# elysium_v0_6.net
KiCad netlist of a schematic drawn in EAGLE
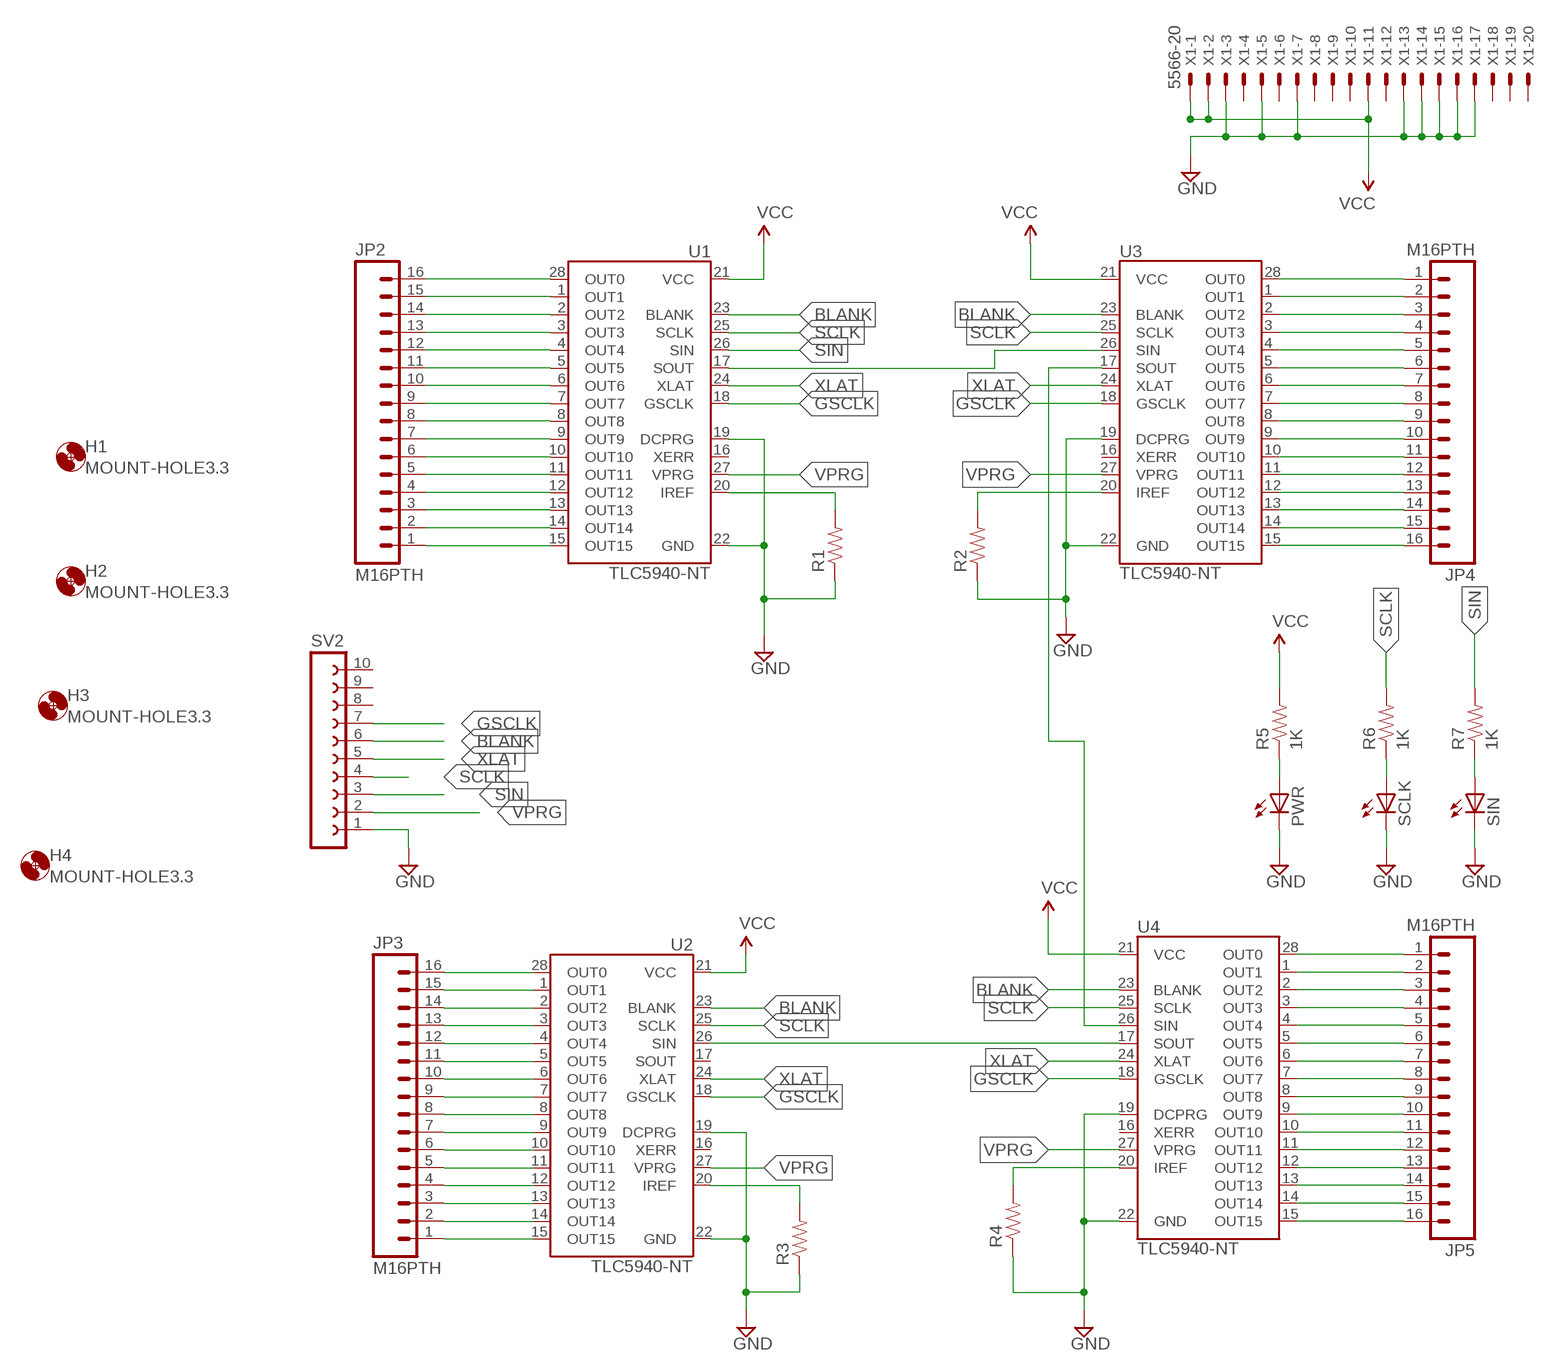
[diagram p0: schematic, sheet 1]

(export (version "E")
  (design (tool "Eeschema 10.0.6"))
  (components
    (comp (ref "H1")
      (value "MOUNT-HOLE3.3")
      (footprint "eagle-import:3,3")
      (libsource (lib "eagle-import") (part "MOUNT-HOLE3.3"))
    )
    (comp (ref "H2")
      (value "MOUNT-HOLE3.3")
      (footprint "eagle-import:3,3")
      (libsource (lib "eagle-import") (part "MOUNT-HOLE3.3"))
    )
    (comp (ref "H3")
      (value "MOUNT-HOLE3.3")
      (footprint "eagle-import:3,3")
      (libsource (lib "eagle-import") (part "MOUNT-HOLE3.3"))
    )
    (comp (ref "H4")
      (value "MOUNT-HOLE3.3")
      (footprint "eagle-import:3,3")
      (libsource (lib "eagle-import") (part "MOUNT-HOLE3.3"))
    )
    (comp (ref "JP2")
      (value "M16PTH")
      (footprint "eagle-import:1X16")
      (libsource (lib "eagle-import") (part "M16PTH"))
    )
    (comp (ref "JP3")
      (value "M16PTH")
      (footprint "eagle-import:1X16")
      (libsource (lib "eagle-import") (part "M16PTH"))
    )
    (comp (ref "JP4")
      (value "M16PTH")
      (footprint "eagle-import:1X16")
      (libsource (lib "eagle-import") (part "M16PTH"))
    )
    (comp (ref "JP5")
      (value "M16PTH")
      (footprint "eagle-import:1X16")
      (libsource (lib "eagle-import") (part "M16PTH"))
    )
    (comp (ref "PWR")
      (value "LED5MM")
      (footprint "eagle-import:LED5MM")
      (libsource (lib "eagle-import") (part "LED5MM"))
    )
    (comp (ref "R1")
      (value "RESISTOREZ")
      (footprint "eagle-import:AXIAL-0.3EZ")
      (libsource (lib "eagle-import") (part "RESISTOREZ"))
    )
    (comp (ref "R2")
      (value "RESISTOREZ")
      (footprint "eagle-import:AXIAL-0.3EZ")
      (libsource (lib "eagle-import") (part "RESISTOREZ"))
    )
    (comp (ref "R3")
      (value "RESISTOREZ")
      (footprint "eagle-import:AXIAL-0.3EZ")
      (libsource (lib "eagle-import") (part "RESISTOREZ"))
    )
    (comp (ref "R4")
      (value "RESISTOREZ")
      (footprint "eagle-import:AXIAL-0.3EZ")
      (libsource (lib "eagle-import") (part "RESISTOREZ"))
    )
    (comp (ref "R5")
      (value "1K")
      (footprint "eagle-import:AXIAL-0.3EZ")
      (libsource (lib "eagle-import") (part "RESISTOREZ"))
    )
    (comp (ref "R6")
      (value "1K")
      (footprint "eagle-import:AXIAL-0.3EZ")
      (libsource (lib "eagle-import") (part "RESISTOREZ"))
    )
    (comp (ref "R7")
      (value "1K")
      (footprint "eagle-import:AXIAL-0.3EZ")
      (libsource (lib "eagle-import") (part "RESISTOREZ"))
    )
    (comp (ref "SCLK")
      (value "LED5MM")
      (footprint "eagle-import:LED5MM")
      (libsource (lib "eagle-import") (part "LED5MM"))
    )
    (comp (ref "SIN")
      (value "LED5MM")
      (footprint "eagle-import:LED5MM")
      (libsource (lib "eagle-import") (part "LED5MM"))
    )
    (comp (ref "SV2")
      (value "FE10-1")
      (footprint "eagle-import:FE10")
      (libsource (lib "eagle-import") (part "FE10-1"))
    )
    (comp (ref "U1")
      (value "TLC5940-NT")
      (footprint "eagle-import:DIL28-3")
      (libsource (lib "eagle-import") (part "TLC5940-NT"))
    )
    (comp (ref "U2")
      (value "TLC5940-NT")
      (footprint "eagle-import:DIL28-3")
      (libsource (lib "eagle-import") (part "TLC5940-NT"))
    )
    (comp (ref "U3")
      (value "TLC5940-NT")
      (footprint "eagle-import:DIL28-3")
      (libsource (lib "eagle-import") (part "TLC5940-NT"))
    )
    (comp (ref "U4")
      (value "TLC5940-NT")
      (footprint "eagle-import:DIL28-3")
      (libsource (lib "eagle-import") (part "TLC5940-NT"))
    )
    (comp (ref "X1")
      (value "5566-20")
      (footprint "eagle-import:5566-20")
      (libsource (lib "eagle-import") (part "5566-20"))
    )
  )
  (nets
    (net (code "1") (name "BLANK") (class "Default")
      (node (ref "SV2") (pin "6") (pinfunction "6_6") (pintype "passive"))
      (node (ref "U1") (pin "23") (pinfunction "BLANK_23") (pintype "bidirectional"))
      (node (ref "U2") (pin "23") (pinfunction "BLANK_23") (pintype "bidirectional"))
      (node (ref "U3") (pin "23") (pinfunction "BLANK_23") (pintype "bidirectional"))
      (node (ref "U4") (pin "23") (pinfunction "BLANK_23") (pintype "bidirectional"))
    )
    (net (code "2") (name "GND") (class "Default")
      (node (ref "PWR") (pin "K") (pinfunction "C_K") (pintype "passive"))
      (node (ref "R1") (pin "P$1") (pinfunction "1_P$1") (pintype "passive"))
      (node (ref "R2") (pin "P$1") (pinfunction "1_P$1") (pintype "passive"))
      (node (ref "R3") (pin "P$1") (pinfunction "1_P$1") (pintype "passive"))
      (node (ref "R4") (pin "P$1") (pinfunction "1_P$1") (pintype "passive"))
      (node (ref "SCLK") (pin "K") (pinfunction "C_K") (pintype "passive"))
      (node (ref "SIN") (pin "K") (pinfunction "C_K") (pintype "passive"))
      (node (ref "SV2") (pin "1") (pinfunction "1_1") (pintype "passive"))
      (node (ref "U1") (pin "19") (pinfunction "DCPRG_19") (pintype "bidirectional"))
      (node (ref "U1") (pin "22") (pinfunction "GND_22") (pintype "bidirectional"))
      (node (ref "U2") (pin "19") (pinfunction "DCPRG_19") (pintype "bidirectional"))
      (node (ref "U2") (pin "22") (pinfunction "GND_22") (pintype "bidirectional"))
      (node (ref "U3") (pin "19") (pinfunction "DCPRG_19") (pintype "bidirectional"))
      (node (ref "U3") (pin "22") (pinfunction "GND_22") (pintype "bidirectional"))
      (node (ref "U4") (pin "19") (pinfunction "DCPRG_19") (pintype "bidirectional"))
      (node (ref "U4") (pin "22") (pinfunction "GND_22") (pintype "bidirectional"))
      (node (ref "X1") (pin "13") (pinfunction "S_13") (pintype "passive"))
      (node (ref "X1") (pin "14") (pinfunction "S_14") (pintype "passive"))
      (node (ref "X1") (pin "15") (pinfunction "S_15") (pintype "passive"))
      (node (ref "X1") (pin "16") (pinfunction "S_16") (pintype "passive"))
      (node (ref "X1") (pin "17") (pinfunction "S_17") (pintype "passive"))
      (node (ref "X1") (pin "3") (pinfunction "S_3") (pintype "passive"))
      (node (ref "X1") (pin "5") (pinfunction "S_5") (pintype "passive"))
      (node (ref "X1") (pin "7") (pinfunction "S_7") (pintype "passive"))
    )
    (net (code "3") (name "GSCLK") (class "Default")
      (node (ref "SV2") (pin "7") (pinfunction "7_7") (pintype "passive"))
      (node (ref "U1") (pin "18") (pinfunction "GSCLK_18") (pintype "bidirectional"))
      (node (ref "U2") (pin "18") (pinfunction "GSCLK_18") (pintype "bidirectional"))
      (node (ref "U3") (pin "18") (pinfunction "GSCLK_18") (pintype "bidirectional"))
      (node (ref "U4") (pin "18") (pinfunction "GSCLK_18") (pintype "bidirectional"))
    )
    (net (code "4") (name "Net-(R1-2)") (class "Default")
      (node (ref "R1") (pin "P$2") (pinfunction "2_P$2") (pintype "passive"))
      (node (ref "U1") (pin "20") (pinfunction "IREF_20") (pintype "bidirectional"))
    )
    (net (code "5") (name "Net-(R2-2)") (class "Default")
      (node (ref "R2") (pin "P$2") (pinfunction "2_P$2") (pintype "passive"))
      (node (ref "U3") (pin "20") (pinfunction "IREF_20") (pintype "bidirectional"))
    )
    (net (code "6") (name "Net-(R3-2)") (class "Default")
      (node (ref "R3") (pin "P$2") (pinfunction "2_P$2") (pintype "passive"))
      (node (ref "U2") (pin "20") (pinfunction "IREF_20") (pintype "bidirectional"))
    )
    (net (code "7") (name "Net-(R4-2)") (class "Default")
      (node (ref "R4") (pin "P$2") (pinfunction "2_P$2") (pintype "passive"))
      (node (ref "U4") (pin "20") (pinfunction "IREF_20") (pintype "bidirectional"))
    )
    (net (code "8") (name "Net-(R5-1)") (class "Default")
      (node (ref "PWR") (pin "A") (pinfunction "A_A") (pintype "passive"))
      (node (ref "R5") (pin "P$1") (pinfunction "1_P$1") (pintype "passive"))
    )
    (net (code "9") (name "Net-(R6-1)") (class "Default")
      (node (ref "R6") (pin "P$1") (pinfunction "1_P$1") (pintype "passive"))
      (node (ref "SCLK") (pin "A") (pinfunction "A_A") (pintype "passive"))
    )
    (net (code "10") (name "Net-(R7-1)") (class "Default")
      (node (ref "R7") (pin "P$1") (pinfunction "1_P$1") (pintype "passive"))
      (node (ref "SIN") (pin "A") (pinfunction "A_A") (pintype "passive"))
    )
    (net (code "11") (name "Net-(U1-OUT0)") (class "Default")
      (node (ref "JP2") (pin "16") (pinfunction "16_16") (pintype "passive"))
      (node (ref "U1") (pin "28") (pinfunction "OUT0_28") (pintype "bidirectional"))
    )
    (net (code "12") (name "Net-(U1-OUT1)") (class "Default")
      (node (ref "JP2") (pin "15") (pinfunction "15_15") (pintype "passive"))
      (node (ref "U1") (pin "1") (pinfunction "OUT1_1") (pintype "bidirectional"))
    )
    (net (code "13") (name "Net-(U1-OUT2)") (class "Default")
      (node (ref "JP2") (pin "14") (pinfunction "14_14") (pintype "passive"))
      (node (ref "U1") (pin "2") (pinfunction "OUT2_2") (pintype "bidirectional"))
    )
    (net (code "14") (name "Net-(U1-OUT3)") (class "Default")
      (node (ref "JP2") (pin "13") (pinfunction "13_13") (pintype "passive"))
      (node (ref "U1") (pin "3") (pinfunction "OUT3_3") (pintype "bidirectional"))
    )
    (net (code "15") (name "Net-(U1-OUT4)") (class "Default")
      (node (ref "JP2") (pin "12") (pinfunction "12_12") (pintype "passive"))
      (node (ref "U1") (pin "4") (pinfunction "OUT4_4") (pintype "bidirectional"))
    )
    (net (code "16") (name "Net-(U1-OUT5)") (class "Default")
      (node (ref "JP2") (pin "11") (pinfunction "11_11") (pintype "passive"))
      (node (ref "U1") (pin "5") (pinfunction "OUT5_5") (pintype "bidirectional"))
    )
    (net (code "17") (name "Net-(U1-OUT6)") (class "Default")
      (node (ref "JP2") (pin "10") (pinfunction "10_10") (pintype "passive"))
      (node (ref "U1") (pin "6") (pinfunction "OUT6_6") (pintype "bidirectional"))
    )
    (net (code "18") (name "Net-(U1-OUT7)") (class "Default")
      (node (ref "JP2") (pin "9") (pinfunction "9_9") (pintype "passive"))
      (node (ref "U1") (pin "7") (pinfunction "OUT7_7") (pintype "bidirectional"))
    )
    (net (code "19") (name "Net-(U1-OUT8)") (class "Default")
      (node (ref "JP2") (pin "8") (pinfunction "8_8") (pintype "passive"))
      (node (ref "U1") (pin "8") (pinfunction "OUT8_8") (pintype "bidirectional"))
    )
    (net (code "20") (name "Net-(U1-OUT9)") (class "Default")
      (node (ref "JP2") (pin "7") (pinfunction "7_7") (pintype "passive"))
      (node (ref "U1") (pin "9") (pinfunction "OUT9_9") (pintype "bidirectional"))
    )
    (net (code "21") (name "Net-(U1-OUT10)") (class "Default")
      (node (ref "JP2") (pin "6") (pinfunction "6_6") (pintype "passive"))
      (node (ref "U1") (pin "10") (pinfunction "OUT10_10") (pintype "bidirectional"))
    )
    (net (code "22") (name "Net-(U1-OUT11)") (class "Default")
      (node (ref "JP2") (pin "5") (pinfunction "5_5") (pintype "passive"))
      (node (ref "U1") (pin "11") (pinfunction "OUT11_11") (pintype "bidirectional"))
    )
    (net (code "23") (name "Net-(U1-OUT12)") (class "Default")
      (node (ref "JP2") (pin "4") (pinfunction "4_4") (pintype "passive"))
      (node (ref "U1") (pin "12") (pinfunction "OUT12_12") (pintype "bidirectional"))
    )
    (net (code "24") (name "Net-(U1-OUT13)") (class "Default")
      (node (ref "JP2") (pin "3") (pinfunction "3_3") (pintype "passive"))
      (node (ref "U1") (pin "13") (pinfunction "OUT13_13") (pintype "bidirectional"))
    )
    (net (code "25") (name "Net-(U1-OUT14)") (class "Default")
      (node (ref "JP2") (pin "2") (pinfunction "2_2") (pintype "passive"))
      (node (ref "U1") (pin "14") (pinfunction "OUT14_14") (pintype "bidirectional"))
    )
    (net (code "26") (name "Net-(U1-OUT15)") (class "Default")
      (node (ref "JP2") (pin "1") (pinfunction "1_1") (pintype "passive"))
      (node (ref "U1") (pin "15") (pinfunction "OUT15_15") (pintype "bidirectional"))
    )
    (net (code "27") (name "Net-(U1-SOUT)") (class "Default")
      (node (ref "U1") (pin "17") (pinfunction "SOUT_17") (pintype "bidirectional"))
      (node (ref "U3") (pin "26") (pinfunction "SIN_26") (pintype "bidirectional"))
    )
    (net (code "28") (name "Net-(U2-OUT0)") (class "Default")
      (node (ref "JP3") (pin "16") (pinfunction "16_16") (pintype "passive"))
      (node (ref "U2") (pin "28") (pinfunction "OUT0_28") (pintype "bidirectional"))
    )
    (net (code "29") (name "Net-(U2-OUT1)") (class "Default")
      (node (ref "JP3") (pin "15") (pinfunction "15_15") (pintype "passive"))
      (node (ref "U2") (pin "1") (pinfunction "OUT1_1") (pintype "bidirectional"))
    )
    (net (code "30") (name "Net-(U2-OUT2)") (class "Default")
      (node (ref "JP3") (pin "14") (pinfunction "14_14") (pintype "passive"))
      (node (ref "U2") (pin "2") (pinfunction "OUT2_2") (pintype "bidirectional"))
    )
    (net (code "31") (name "Net-(U2-OUT3)") (class "Default")
      (node (ref "JP3") (pin "13") (pinfunction "13_13") (pintype "passive"))
      (node (ref "U2") (pin "3") (pinfunction "OUT3_3") (pintype "bidirectional"))
    )
    (net (code "32") (name "Net-(U2-OUT4)") (class "Default")
      (node (ref "JP3") (pin "12") (pinfunction "12_12") (pintype "passive"))
      (node (ref "U2") (pin "4") (pinfunction "OUT4_4") (pintype "bidirectional"))
    )
    (net (code "33") (name "Net-(U2-OUT5)") (class "Default")
      (node (ref "JP3") (pin "11") (pinfunction "11_11") (pintype "passive"))
      (node (ref "U2") (pin "5") (pinfunction "OUT5_5") (pintype "bidirectional"))
    )
    (net (code "34") (name "Net-(U2-OUT6)") (class "Default")
      (node (ref "JP3") (pin "10") (pinfunction "10_10") (pintype "passive"))
      (node (ref "U2") (pin "6") (pinfunction "OUT6_6") (pintype "bidirectional"))
    )
    (net (code "35") (name "Net-(U2-OUT7)") (class "Default")
      (node (ref "JP3") (pin "9") (pinfunction "9_9") (pintype "passive"))
      (node (ref "U2") (pin "7") (pinfunction "OUT7_7") (pintype "bidirectional"))
    )
    (net (code "36") (name "Net-(U2-OUT8)") (class "Default")
      (node (ref "JP3") (pin "8") (pinfunction "8_8") (pintype "passive"))
      (node (ref "U2") (pin "8") (pinfunction "OUT8_8") (pintype "bidirectional"))
    )
    (net (code "37") (name "Net-(U2-OUT9)") (class "Default")
      (node (ref "JP3") (pin "7") (pinfunction "7_7") (pintype "passive"))
      (node (ref "U2") (pin "9") (pinfunction "OUT9_9") (pintype "bidirectional"))
    )
    (net (code "38") (name "Net-(U2-OUT10)") (class "Default")
      (node (ref "JP3") (pin "6") (pinfunction "6_6") (pintype "passive"))
      (node (ref "U2") (pin "10") (pinfunction "OUT10_10") (pintype "bidirectional"))
    )
    (net (code "39") (name "Net-(U2-OUT11)") (class "Default")
      (node (ref "JP3") (pin "5") (pinfunction "5_5") (pintype "passive"))
      (node (ref "U2") (pin "11") (pinfunction "OUT11_11") (pintype "bidirectional"))
    )
    (net (code "40") (name "Net-(U2-OUT12)") (class "Default")
      (node (ref "JP3") (pin "4") (pinfunction "4_4") (pintype "passive"))
      (node (ref "U2") (pin "12") (pinfunction "OUT12_12") (pintype "bidirectional"))
    )
    (net (code "41") (name "Net-(U2-OUT13)") (class "Default")
      (node (ref "JP3") (pin "3") (pinfunction "3_3") (pintype "passive"))
      (node (ref "U2") (pin "13") (pinfunction "OUT13_13") (pintype "bidirectional"))
    )
    (net (code "42") (name "Net-(U2-OUT14)") (class "Default")
      (node (ref "JP3") (pin "2") (pinfunction "2_2") (pintype "passive"))
      (node (ref "U2") (pin "14") (pinfunction "OUT14_14") (pintype "bidirectional"))
    )
    (net (code "43") (name "Net-(U2-OUT15)") (class "Default")
      (node (ref "JP3") (pin "1") (pinfunction "1_1") (pintype "passive"))
      (node (ref "U2") (pin "15") (pinfunction "OUT15_15") (pintype "bidirectional"))
    )
    (net (code "44") (name "Net-(U2-SIN)") (class "Default")
      (node (ref "U2") (pin "26") (pinfunction "SIN_26") (pintype "bidirectional"))
      (node (ref "U4") (pin "17") (pinfunction "SOUT_17") (pintype "bidirectional"))
    )
    (net (code "45") (name "Net-(U3-OUT0)") (class "Default")
      (node (ref "JP4") (pin "1") (pinfunction "1_1") (pintype "passive"))
      (node (ref "U3") (pin "28") (pinfunction "OUT0_28") (pintype "bidirectional"))
    )
    (net (code "46") (name "Net-(U3-OUT1)") (class "Default")
      (node (ref "JP4") (pin "2") (pinfunction "2_2") (pintype "passive"))
      (node (ref "U3") (pin "1") (pinfunction "OUT1_1") (pintype "bidirectional"))
    )
    (net (code "47") (name "Net-(U3-OUT2)") (class "Default")
      (node (ref "JP4") (pin "3") (pinfunction "3_3") (pintype "passive"))
      (node (ref "U3") (pin "2") (pinfunction "OUT2_2") (pintype "bidirectional"))
    )
    (net (code "48") (name "Net-(U3-OUT3)") (class "Default")
      (node (ref "JP4") (pin "4") (pinfunction "4_4") (pintype "passive"))
      (node (ref "U3") (pin "3") (pinfunction "OUT3_3") (pintype "bidirectional"))
    )
    (net (code "49") (name "Net-(U3-OUT4)") (class "Default")
      (node (ref "JP4") (pin "5") (pinfunction "5_5") (pintype "passive"))
      (node (ref "U3") (pin "4") (pinfunction "OUT4_4") (pintype "bidirectional"))
    )
    (net (code "50") (name "Net-(U3-OUT5)") (class "Default")
      (node (ref "JP4") (pin "6") (pinfunction "6_6") (pintype "passive"))
      (node (ref "U3") (pin "5") (pinfunction "OUT5_5") (pintype "bidirectional"))
    )
    (net (code "51") (name "Net-(U3-OUT6)") (class "Default")
      (node (ref "JP4") (pin "7") (pinfunction "7_7") (pintype "passive"))
      (node (ref "U3") (pin "6") (pinfunction "OUT6_6") (pintype "bidirectional"))
    )
    (net (code "52") (name "Net-(U3-OUT7)") (class "Default")
      (node (ref "JP4") (pin "8") (pinfunction "8_8") (pintype "passive"))
      (node (ref "U3") (pin "7") (pinfunction "OUT7_7") (pintype "bidirectional"))
    )
    (net (code "53") (name "Net-(U3-OUT8)") (class "Default")
      (node (ref "JP4") (pin "9") (pinfunction "9_9") (pintype "passive"))
      (node (ref "U3") (pin "8") (pinfunction "OUT8_8") (pintype "bidirectional"))
    )
    (net (code "54") (name "Net-(U3-OUT9)") (class "Default")
      (node (ref "JP4") (pin "10") (pinfunction "10_10") (pintype "passive"))
      (node (ref "U3") (pin "9") (pinfunction "OUT9_9") (pintype "bidirectional"))
    )
    (net (code "55") (name "Net-(U3-OUT10)") (class "Default")
      (node (ref "JP4") (pin "11") (pinfunction "11_11") (pintype "passive"))
      (node (ref "U3") (pin "10") (pinfunction "OUT10_10") (pintype "bidirectional"))
    )
    (net (code "56") (name "Net-(U3-OUT11)") (class "Default")
      (node (ref "JP4") (pin "12") (pinfunction "12_12") (pintype "passive"))
      (node (ref "U3") (pin "11") (pinfunction "OUT11_11") (pintype "bidirectional"))
    )
    (net (code "57") (name "Net-(U3-OUT12)") (class "Default")
      (node (ref "JP4") (pin "13") (pinfunction "13_13") (pintype "passive"))
      (node (ref "U3") (pin "12") (pinfunction "OUT12_12") (pintype "bidirectional"))
    )
    (net (code "58") (name "Net-(U3-OUT13)") (class "Default")
      (node (ref "JP4") (pin "14") (pinfunction "14_14") (pintype "passive"))
      (node (ref "U3") (pin "13") (pinfunction "OUT13_13") (pintype "bidirectional"))
    )
    (net (code "59") (name "Net-(U3-OUT14)") (class "Default")
      (node (ref "JP4") (pin "15") (pinfunction "15_15") (pintype "passive"))
      (node (ref "U3") (pin "14") (pinfunction "OUT14_14") (pintype "bidirectional"))
    )
    (net (code "60") (name "Net-(U3-OUT15)") (class "Default")
      (node (ref "JP4") (pin "16") (pinfunction "16_16") (pintype "passive"))
      (node (ref "U3") (pin "15") (pinfunction "OUT15_15") (pintype "bidirectional"))
    )
    (net (code "61") (name "Net-(U3-SOUT)") (class "Default")
      (node (ref "U3") (pin "17") (pinfunction "SOUT_17") (pintype "bidirectional"))
      (node (ref "U4") (pin "26") (pinfunction "SIN_26") (pintype "bidirectional"))
    )
    (net (code "62") (name "Net-(U4-OUT0)") (class "Default")
      (node (ref "JP5") (pin "1") (pinfunction "1_1") (pintype "passive"))
      (node (ref "U4") (pin "28") (pinfunction "OUT0_28") (pintype "bidirectional"))
    )
    (net (code "63") (name "Net-(U4-OUT1)") (class "Default")
      (node (ref "JP5") (pin "2") (pinfunction "2_2") (pintype "passive"))
      (node (ref "U4") (pin "1") (pinfunction "OUT1_1") (pintype "bidirectional"))
    )
    (net (code "64") (name "Net-(U4-OUT2)") (class "Default")
      (node (ref "JP5") (pin "3") (pinfunction "3_3") (pintype "passive"))
      (node (ref "U4") (pin "2") (pinfunction "OUT2_2") (pintype "bidirectional"))
    )
    (net (code "65") (name "Net-(U4-OUT3)") (class "Default")
      (node (ref "JP5") (pin "4") (pinfunction "4_4") (pintype "passive"))
      (node (ref "U4") (pin "3") (pinfunction "OUT3_3") (pintype "bidirectional"))
    )
    (net (code "66") (name "Net-(U4-OUT4)") (class "Default")
      (node (ref "JP5") (pin "5") (pinfunction "5_5") (pintype "passive"))
      (node (ref "U4") (pin "4") (pinfunction "OUT4_4") (pintype "bidirectional"))
    )
    (net (code "67") (name "Net-(U4-OUT5)") (class "Default")
      (node (ref "JP5") (pin "6") (pinfunction "6_6") (pintype "passive"))
      (node (ref "U4") (pin "5") (pinfunction "OUT5_5") (pintype "bidirectional"))
    )
    (net (code "68") (name "Net-(U4-OUT6)") (class "Default")
      (node (ref "JP5") (pin "7") (pinfunction "7_7") (pintype "passive"))
      (node (ref "U4") (pin "6") (pinfunction "OUT6_6") (pintype "bidirectional"))
    )
    (net (code "69") (name "Net-(U4-OUT7)") (class "Default")
      (node (ref "JP5") (pin "8") (pinfunction "8_8") (pintype "passive"))
      (node (ref "U4") (pin "7") (pinfunction "OUT7_7") (pintype "bidirectional"))
    )
    (net (code "70") (name "Net-(U4-OUT8)") (class "Default")
      (node (ref "JP5") (pin "9") (pinfunction "9_9") (pintype "passive"))
      (node (ref "U4") (pin "8") (pinfunction "OUT8_8") (pintype "bidirectional"))
    )
    (net (code "71") (name "Net-(U4-OUT9)") (class "Default")
      (node (ref "JP5") (pin "10") (pinfunction "10_10") (pintype "passive"))
      (node (ref "U4") (pin "9") (pinfunction "OUT9_9") (pintype "bidirectional"))
    )
    (net (code "72") (name "Net-(U4-OUT10)") (class "Default")
      (node (ref "JP5") (pin "11") (pinfunction "11_11") (pintype "passive"))
      (node (ref "U4") (pin "10") (pinfunction "OUT10_10") (pintype "bidirectional"))
    )
    (net (code "73") (name "Net-(U4-OUT11)") (class "Default")
      (node (ref "JP5") (pin "12") (pinfunction "12_12") (pintype "passive"))
      (node (ref "U4") (pin "11") (pinfunction "OUT11_11") (pintype "bidirectional"))
    )
    (net (code "74") (name "Net-(U4-OUT12)") (class "Default")
      (node (ref "JP5") (pin "13") (pinfunction "13_13") (pintype "passive"))
      (node (ref "U4") (pin "12") (pinfunction "OUT12_12") (pintype "bidirectional"))
    )
    (net (code "75") (name "Net-(U4-OUT13)") (class "Default")
      (node (ref "JP5") (pin "14") (pinfunction "14_14") (pintype "passive"))
      (node (ref "U4") (pin "13") (pinfunction "OUT13_13") (pintype "bidirectional"))
    )
    (net (code "76") (name "Net-(U4-OUT14)") (class "Default")
      (node (ref "JP5") (pin "15") (pinfunction "15_15") (pintype "passive"))
      (node (ref "U4") (pin "14") (pinfunction "OUT14_14") (pintype "bidirectional"))
    )
    (net (code "77") (name "Net-(U4-OUT15)") (class "Default")
      (node (ref "JP5") (pin "16") (pinfunction "16_16") (pintype "passive"))
      (node (ref "U4") (pin "15") (pinfunction "OUT15_15") (pintype "bidirectional"))
    )
    (net (code "78") (name "SCLK") (class "Default")
      (node (ref "R6") (pin "P$2") (pinfunction "2_P$2") (pintype "passive"))
      (node (ref "SV2") (pin "4") (pinfunction "4_4") (pintype "passive"))
      (node (ref "U1") (pin "25") (pinfunction "SCLK_25") (pintype "bidirectional"))
      (node (ref "U2") (pin "25") (pinfunction "SCLK_25") (pintype "bidirectional"))
      (node (ref "U3") (pin "25") (pinfunction "SCLK_25") (pintype "bidirectional"))
      (node (ref "U4") (pin "25") (pinfunction "SCLK_25") (pintype "bidirectional"))
    )
    (net (code "79") (name "SIN") (class "Default")
      (node (ref "R7") (pin "P$2") (pinfunction "2_P$2") (pintype "passive"))
      (node (ref "SV2") (pin "3") (pinfunction "3_3") (pintype "passive"))
      (node (ref "U1") (pin "26") (pinfunction "SIN_26") (pintype "bidirectional"))
    )
    (net (code "80") (name "VCC") (class "Default")
      (node (ref "R5") (pin "P$2") (pinfunction "2_P$2") (pintype "passive"))
      (node (ref "U1") (pin "21") (pinfunction "VCC_21") (pintype "bidirectional"))
      (node (ref "U2") (pin "21") (pinfunction "VCC_21") (pintype "bidirectional"))
      (node (ref "U3") (pin "21") (pinfunction "VCC_21") (pintype "bidirectional"))
      (node (ref "U4") (pin "21") (pinfunction "VCC_21") (pintype "bidirectional"))
      (node (ref "X1") (pin "1") (pinfunction "S_1") (pintype "passive"))
      (node (ref "X1") (pin "11") (pinfunction "S_11") (pintype "passive"))
      (node (ref "X1") (pin "2") (pinfunction "S_2") (pintype "passive"))
    )
    (net (code "81") (name "VPRG") (class "Default")
      (node (ref "SV2") (pin "2") (pinfunction "2_2") (pintype "passive"))
      (node (ref "U1") (pin "27") (pinfunction "VPRG_27") (pintype "bidirectional"))
      (node (ref "U2") (pin "27") (pinfunction "VPRG_27") (pintype "bidirectional"))
      (node (ref "U3") (pin "27") (pinfunction "VPRG_27") (pintype "bidirectional"))
      (node (ref "U4") (pin "27") (pinfunction "VPRG_27") (pintype "bidirectional"))
    )
    (net (code "82") (name "XLAT") (class "Default")
      (node (ref "SV2") (pin "5") (pinfunction "5_5") (pintype "passive"))
      (node (ref "U1") (pin "24") (pinfunction "XLAT_24") (pintype "bidirectional"))
      (node (ref "U2") (pin "24") (pinfunction "XLAT_24") (pintype "bidirectional"))
      (node (ref "U3") (pin "24") (pinfunction "XLAT_24") (pintype "bidirectional"))
      (node (ref "U4") (pin "24") (pinfunction "XLAT_24") (pintype "bidirectional"))
    )
    (net (code "83") (name "unconnected-(SV2-Pad8)") (class "Default")
      (node (ref "SV2") (pin "8") (pinfunction "8_8") (pintype "passive"))
    )
    (net (code "84") (name "unconnected-(SV2-Pad9)") (class "Default")
      (node (ref "SV2") (pin "9") (pinfunction "9_9") (pintype "passive"))
    )
    (net (code "85") (name "unconnected-(SV2-Pad10)") (class "Default")
      (node (ref "SV2") (pin "10") (pinfunction "10_10") (pintype "passive"))
    )
    (net (code "86") (name "unconnected-(U1-XERR-Pad16)") (class "Default")
      (node (ref "U1") (pin "16") (pinfunction "XERR_16") (pintype "bidirectional"))
    )
    (net (code "87") (name "unconnected-(U2-SOUT-Pad17)") (class "Default")
      (node (ref "U2") (pin "17") (pinfunction "SOUT_17") (pintype "bidirectional"))
    )
    (net (code "88") (name "unconnected-(U2-XERR-Pad16)") (class "Default")
      (node (ref "U2") (pin "16") (pinfunction "XERR_16") (pintype "bidirectional"))
    )
    (net (code "89") (name "unconnected-(U3-XERR-Pad16)") (class "Default")
      (node (ref "U3") (pin "16") (pinfunction "XERR_16") (pintype "bidirectional"))
    )
    (net (code "90") (name "unconnected-(U4-XERR-Pad16)") (class "Default")
      (node (ref "U4") (pin "16") (pinfunction "XERR_16") (pintype "bidirectional"))
    )
    (net (code "91") (name "unconnected-(X1B-S-Pad10)") (class "Default")
      (node (ref "X1") (pin "10") (pinfunction "S_10") (pintype "passive"))
    )
    (net (code "92") (name "unconnected-(X1D-S-Pad12)") (class "Default")
      (node (ref "X1") (pin "12") (pinfunction "S_12") (pintype "passive"))
    )
    (net (code "93") (name "unconnected-(X1J-S-Pad18)") (class "Default")
      (node (ref "X1") (pin "18") (pinfunction "S_18") (pintype "passive"))
    )
    (net (code "94") (name "unconnected-(X1K-S-Pad19)") (class "Default")
      (node (ref "X1") (pin "19") (pinfunction "S_19") (pintype "passive"))
    )
    (net (code "95") (name "unconnected-(X1M-S-Pad20)") (class "Default")
      (node (ref "X1") (pin "20") (pinfunction "S_20") (pintype "passive"))
    )
    (net (code "96") (name "unconnected-(X1O-S-Pad4)") (class "Default")
      (node (ref "X1") (pin "4") (pinfunction "S_4") (pintype "passive"))
    )
    (net (code "97") (name "unconnected-(X1Q-S-Pad6)") (class "Default")
      (node (ref "X1") (pin "6") (pinfunction "S_6") (pintype "passive"))
    )
    (net (code "98") (name "unconnected-(X1S-S-Pad8)") (class "Default")
      (node (ref "X1") (pin "8") (pinfunction "S_8") (pintype "passive"))
    )
    (net (code "99") (name "unconnected-(X1T-S-Pad9)") (class "Default")
      (node (ref "X1") (pin "9") (pinfunction "S_9") (pintype "passive"))
    )
  )
)
